# RCSfullschematic1.net
KiCad netlist of a schematic drawn in EAGLE
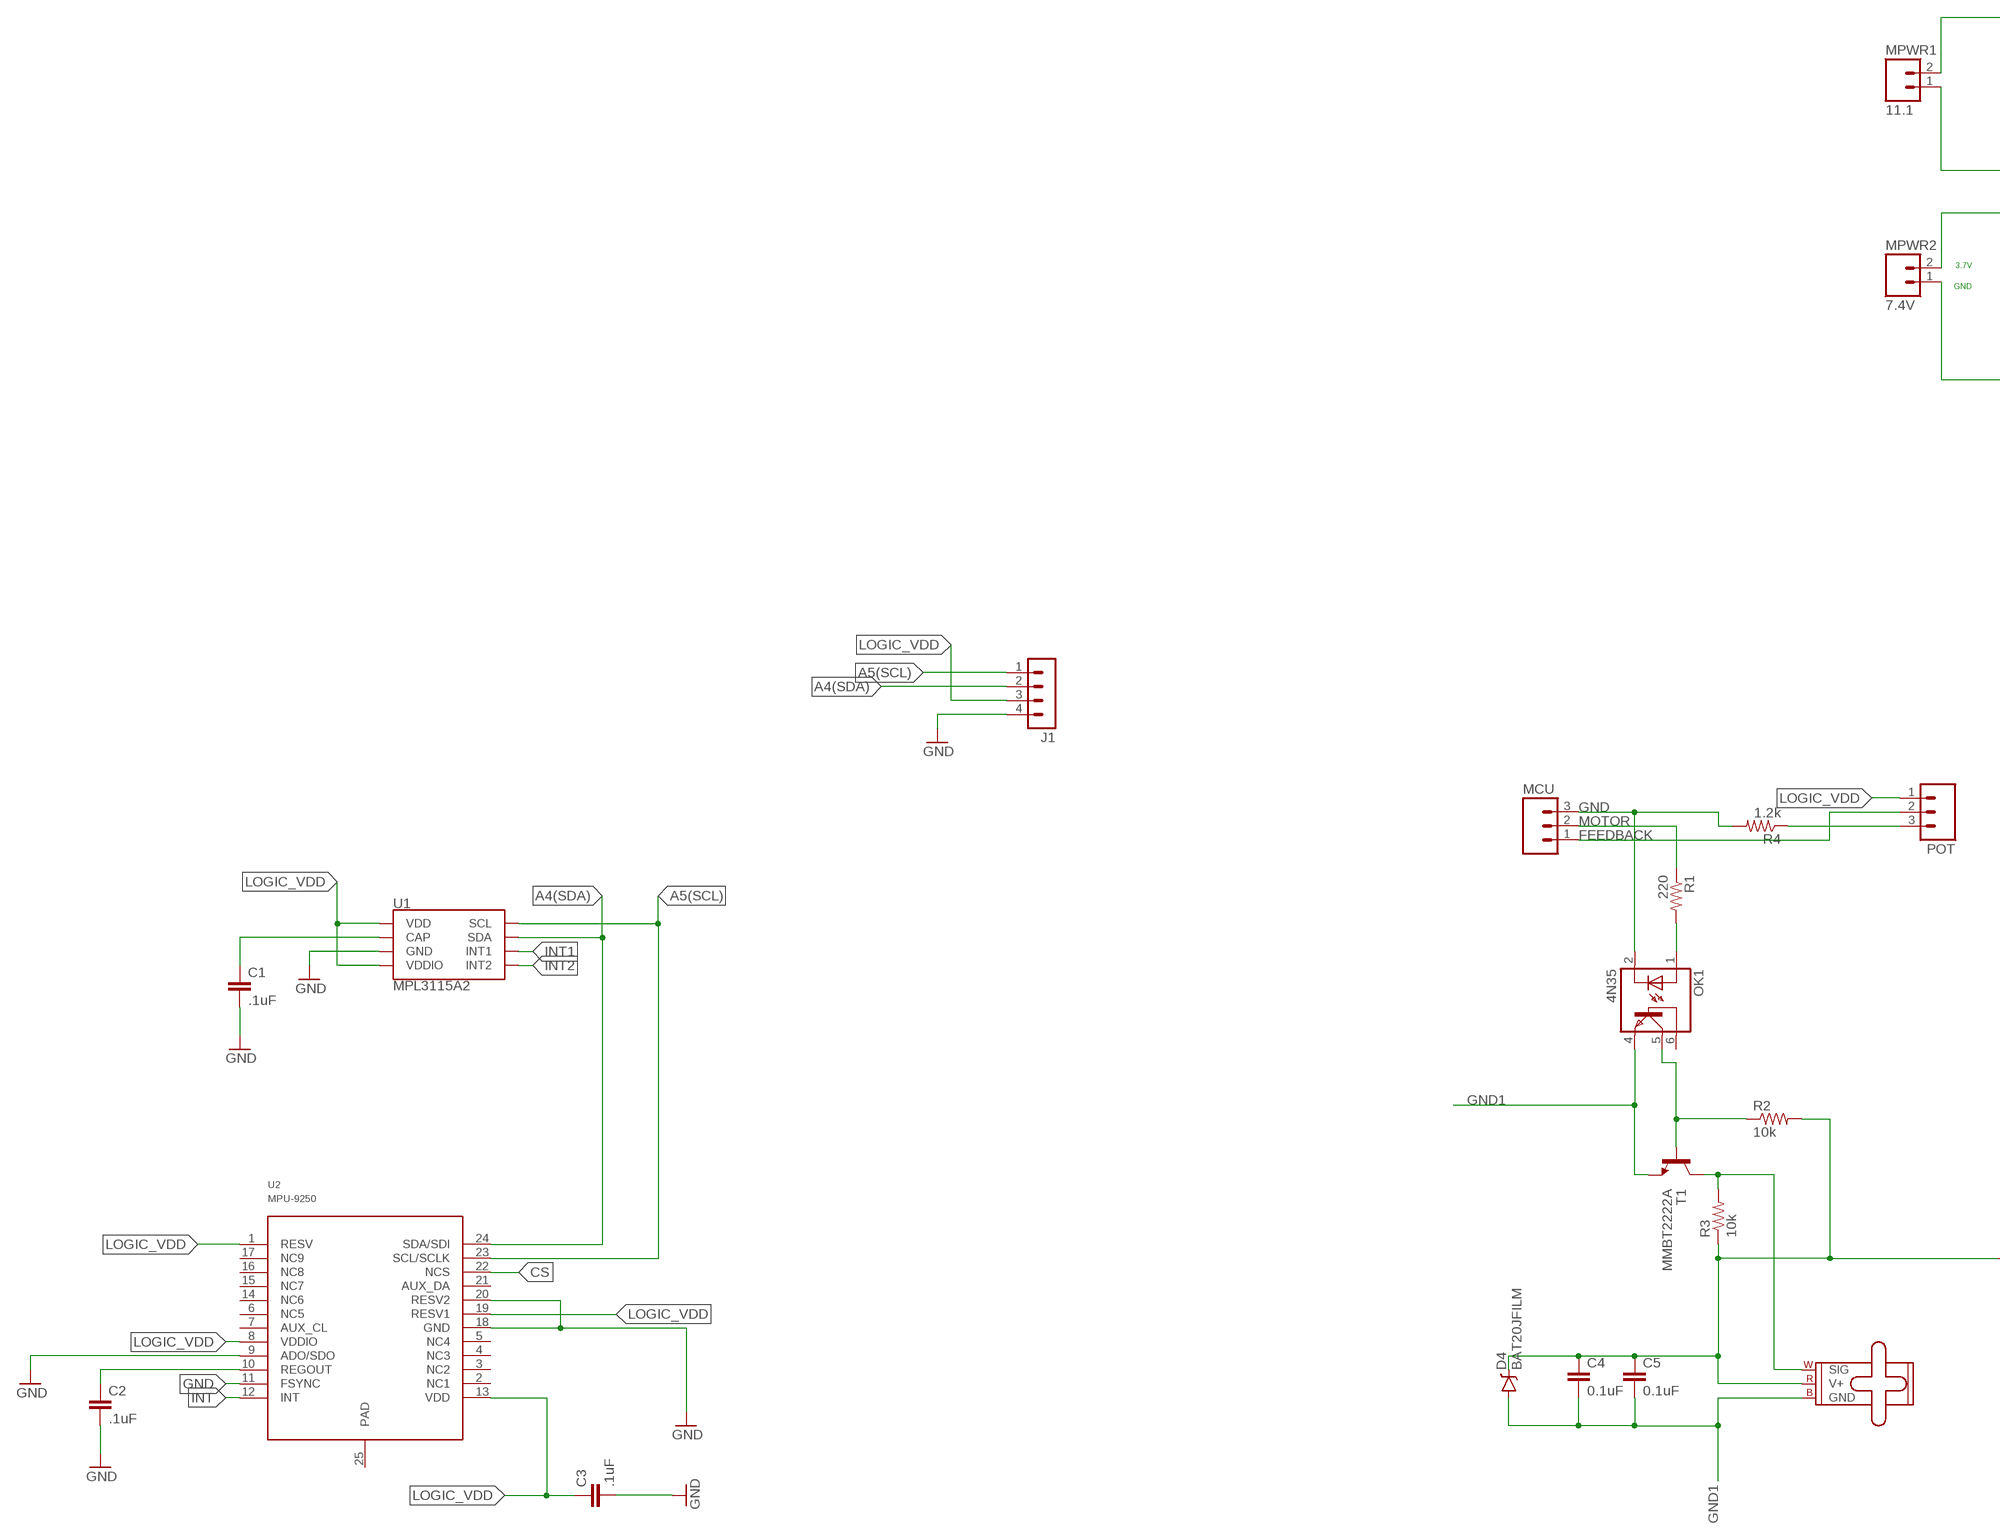
[diagram p0: schematic, sheet 1, part 1 of 2]
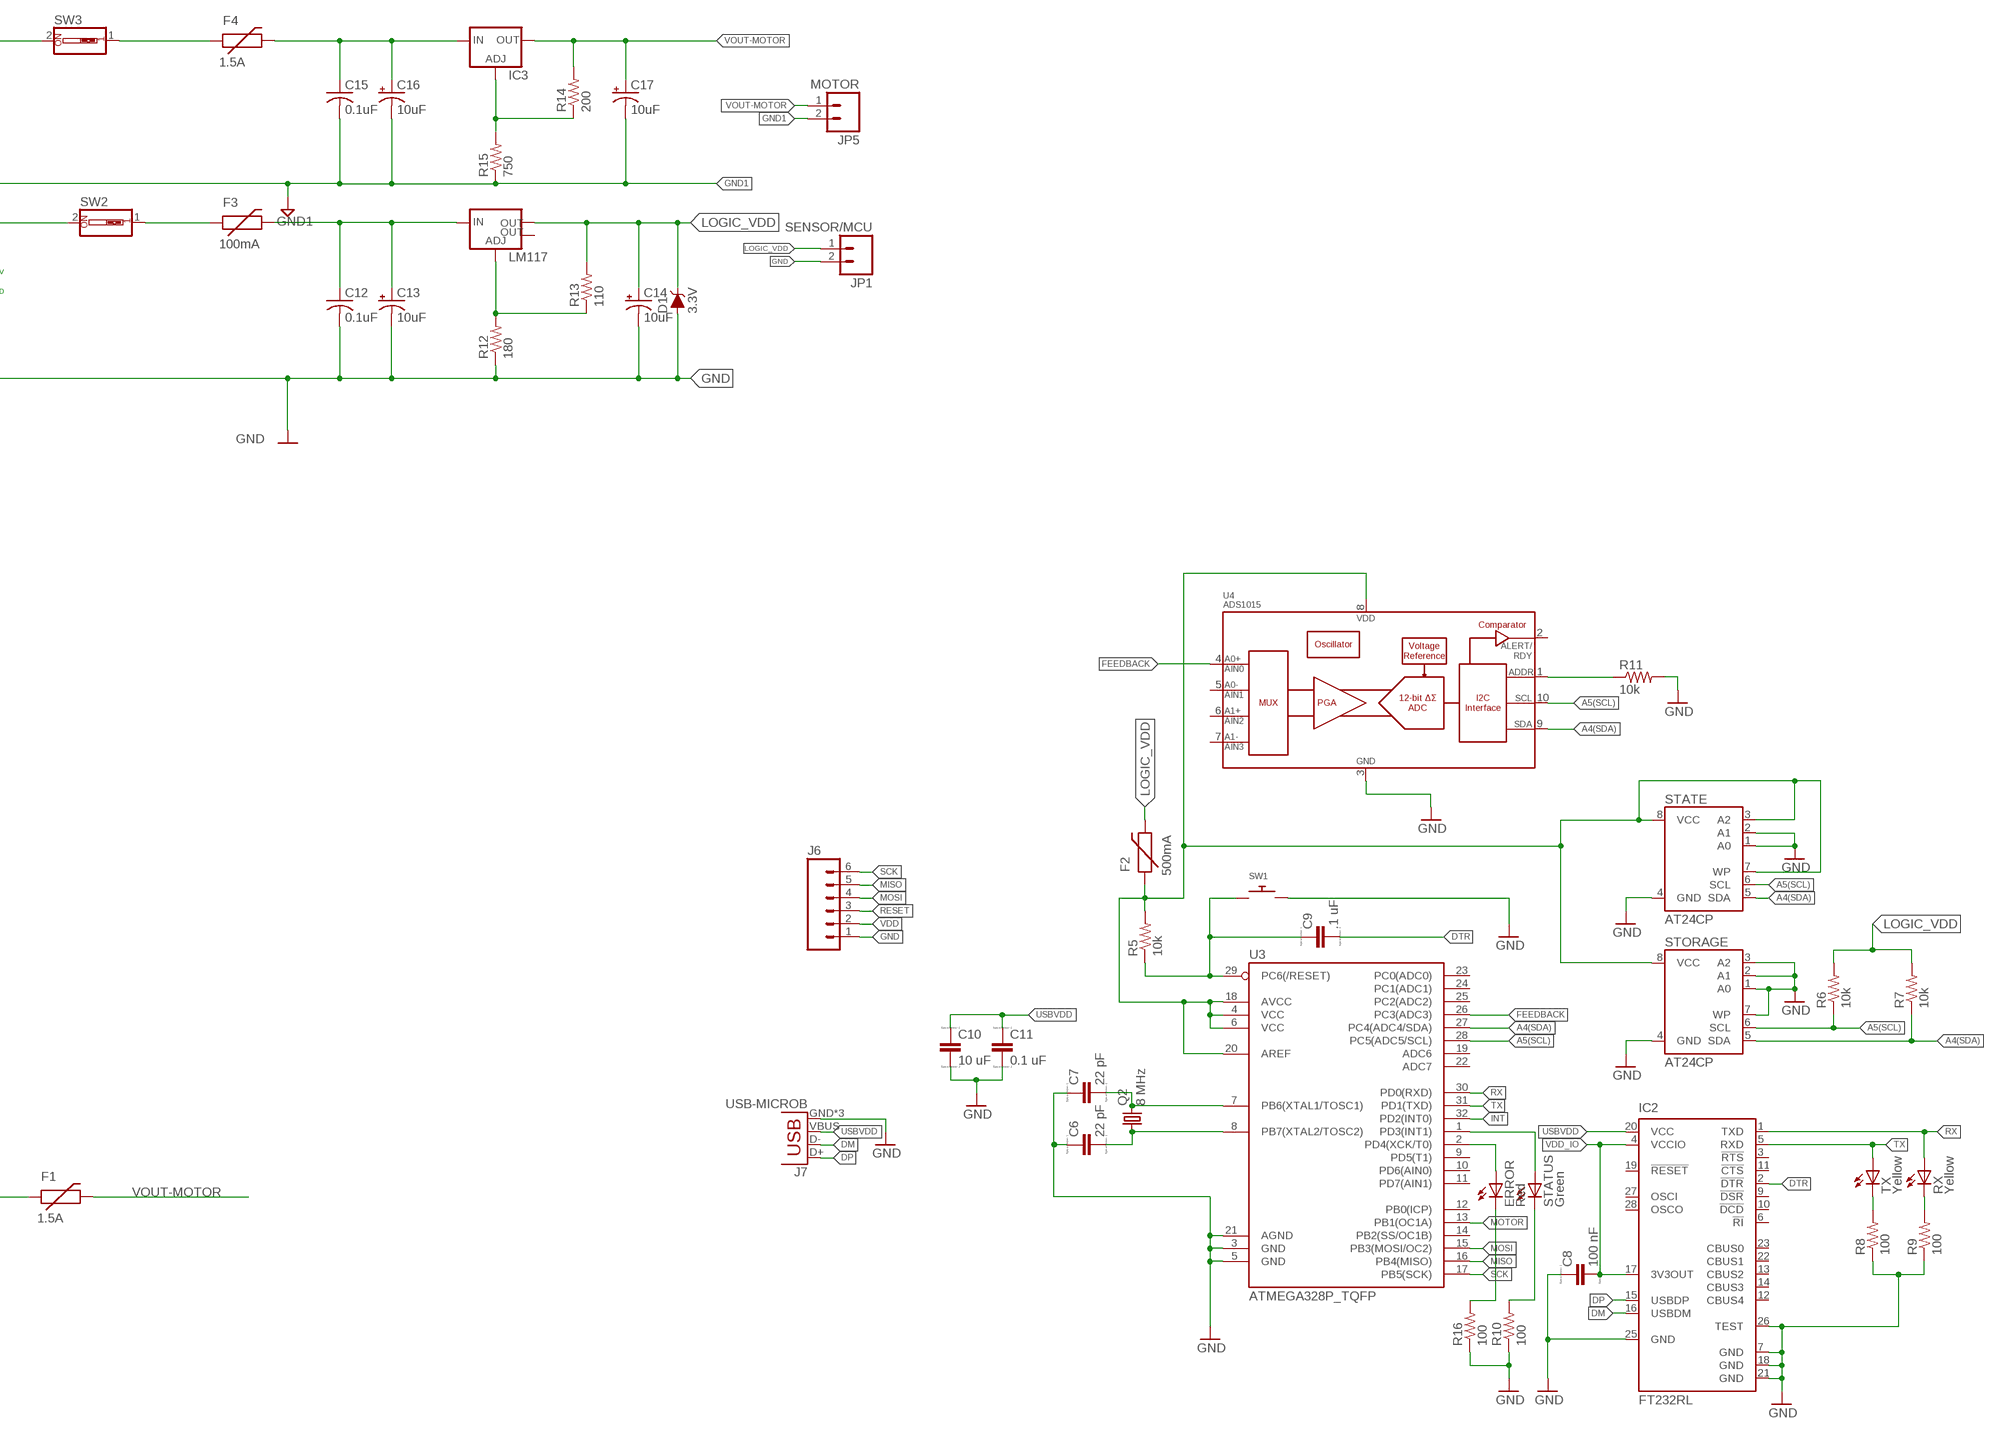
[diagram p1: schematic, sheet 1, part 2 of 2]

(export (version "E")
  (design (tool "Eeschema 10.0.6"))
  (components
    (comp (ref "C1")
      (value ".1uF")
      (footprint "eagle-import:1206")
      (libsource (lib "eagle-import") (part "10UF-1206-6.3V-20%"))
    )
    (comp (ref "C2")
      (value ".1uF")
      (footprint "eagle-import:1206")
      (libsource (lib "eagle-import") (part "10UF-1206-6.3V-20%"))
    )
    (comp (ref "C3")
      (value ".1uF")
      (footprint "eagle-import:1206")
      (libsource (lib "eagle-import") (part "10UF-1206-6.3V-20%"))
    )
    (comp (ref "C4")
      (value "0.1uF")
      (footprint "eagle-import:1206")
      (libsource (lib "eagle-import") (part "CAP1206"))
    )
    (comp (ref "C5")
      (value "0.1uF")
      (footprint "eagle-import:1206")
      (libsource (lib "eagle-import") (part "CAP1206"))
    )
    (comp (ref "C6")
      (value "22 pF")
      (footprint "eagle-import:C1206")
      (libsource (lib "eagle-import") (part "CC1206"))
    )
    (comp (ref "C7")
      (value "22 pF")
      (footprint "eagle-import:C1206")
      (libsource (lib "eagle-import") (part "CC1206"))
    )
    (comp (ref "C8")
      (value "100 nF")
      (footprint "eagle-import:C1206")
      (libsource (lib "eagle-import") (part "CC1206"))
    )
    (comp (ref "C9")
      (value ".1 uF")
      (footprint "eagle-import:C1206")
      (libsource (lib "eagle-import") (part "CC1206"))
    )
    (comp (ref "C10")
      (value "10 uF")
      (footprint "eagle-import:C1206")
      (libsource (lib "eagle-import") (part "CC1206"))
    )
    (comp (ref "C11")
      (value "0.1 uF")
      (footprint "eagle-import:C1206")
      (libsource (lib "eagle-import") (part "CC1206"))
    )
    (comp (ref "C12")
      (value "0.1uF")
      (footprint "eagle-import:C1206")
      (libsource (lib "eagle-import") (part "C-USC1206"))
    )
    (comp (ref "C13")
      (value "10uF")
      (footprint "eagle-import:EIA3216")
      (libsource (lib "eagle-import") (part "10UF-POLAR-EIA3216-16V-10%(TANT)"))
    )
    (comp (ref "C14")
      (value "10uF")
      (footprint "eagle-import:EIA3216")
      (libsource (lib "eagle-import") (part "10UF-POLAR-EIA3216-16V-10%(TANT)"))
    )
    (comp (ref "C15")
      (value "0.1uF")
      (footprint "eagle-import:C1206")
      (libsource (lib "eagle-import") (part "C-USC1206"))
    )
    (comp (ref "C16")
      (value "10uF")
      (footprint "eagle-import:EIA3216")
      (libsource (lib "eagle-import") (part "10UF-POLAR-EIA3216-16V-10%(TANT)"))
    )
    (comp (ref "C17")
      (value "10uF")
      (footprint "eagle-import:EIA3216")
      (libsource (lib "eagle-import") (part "10UF-POLAR-EIA3216-16V-10%(TANT)"))
    )
    (comp (ref "D1")
      (value "3.3V")
      (footprint "eagle-import:SOD-323@2")
      (libsource (lib "eagle-import") (part "DIODE-ZENER-BZT52C3V6S"))
    )
    (comp (ref "D4")
      (value "BAT20JFILM")
      (footprint "eagle-import:SOD-323")
      (libsource (lib "eagle-import") (part "BAT20JFILM"))
    )
    (comp (ref "ERROR")
      (value "Red")
      (footprint "eagle-import:CHIPLED_1206")
      (libsource (lib "eagle-import") (part "LEDCHIPLED_1206"))
    )
    (comp (ref "F1")
      (value "1.5A")
      (footprint "eagle-import:PTC-1206")
      (libsource (lib "eagle-import") (part "PTCSMD"))
    )
    (comp (ref "F2")
      (value "500mA")
      (footprint "eagle-import:PTC-1206")
      (libsource (lib "eagle-import") (part "PTCSMD"))
    )
    (comp (ref "F3")
      (value "100mA")
      (footprint "eagle-import:PTC-1206")
      (libsource (lib "eagle-import") (part "PTCSMD"))
    )
    (comp (ref "F4")
      (value "1.5A")
      (footprint "eagle-import:PTC-1206")
      (libsource (lib "eagle-import") (part "PTCSMD"))
    )
    (comp (ref "IC2")
      (value "FT232RL")
      (footprint "eagle-import:SSOP28")
      (libsource (lib "eagle-import") (part "FT232RL"))
    )
    (comp (ref "IC3")
      (value "LM317TS")
      (footprint "eagle-import:317TS")
      (libsource (lib "eagle-import") (part "LM317TS"))
    )
    (comp (ref "J1")
      (value "MA04-1")
      (footprint "eagle-import:MA04-1")
      (libsource (lib "eagle-import") (part "MA04-1"))
    )
    (comp (ref "J6")
      (value "M06LOCK")
      (footprint "eagle-import:1X06_LOCK")
      (libsource (lib "eagle-import") (part "M06LOCK"))
    )
    (comp (ref "J7")
      (value "USB-MICROB")
      (footprint "eagle-import:USB-MICROB")
      (libsource (lib "eagle-import") (part "USB-MICROB"))
    )
    (comp (ref "JP1")
      (value "SENSOR/MCU")
      (footprint "eagle-import:1X02")
      (libsource (lib "eagle-import") (part "M02PTH"))
    )
    (comp (ref "JP5")
      (value "MOTOR")
      (footprint "eagle-import:1X02")
      (libsource (lib "eagle-import") (part "M02PTH"))
    )
    (comp (ref "LM117")
      (value "V_REG_LM1117SOT223")
      (footprint "eagle-import:SOT223")
      (libsource (lib "eagle-import") (part "V_REG_LM1117SOT223"))
    )
    (comp (ref "MCU")
      (value "M03PTH")
      (footprint "eagle-import:1X03")
      (libsource (lib "eagle-import") (part "M03PTH"))
    )
    (comp (ref "MPWR1")
      (value "11.1")
      (footprint "eagle-import:1X02")
      (libsource (lib "eagle-import") (part "M02PTH"))
    )
    (comp (ref "MPWR2")
      (value "7.4V")
      (footprint "eagle-import:1X02")
      (libsource (lib "eagle-import") (part "M02PTH"))
    )
    (comp (ref "OK1")
      (value "4N35")
      (footprint "eagle-import:DIL06")
      (fields (field (name "MF") "FAIRCHILD SEMICONDUCTOR"))
      (libsource (lib "eagle-import") (part "4N35"))
    )
    (comp (ref "POT")
      (value "M03PTH")
      (footprint "eagle-import:1X03")
      (libsource (lib "eagle-import") (part "M03PTH"))
    )
    (comp (ref "Q2")
      (value "8 MHz")
      (footprint "eagle-import:HC49_S")
      (libsource (lib "eagle-import") (part "CRYSTALHC49S"))
    )
    (comp (ref "R1")
      (value "220")
      (footprint "eagle-import:1206")
      (libsource (lib "eagle-import") (part "RESISTOR1206"))
    )
    (comp (ref "R2")
      (value "10k")
      (footprint "eagle-import:1206")
      (libsource (lib "eagle-import") (part "RESISTOR1206"))
    )
    (comp (ref "R3")
      (value "10k")
      (footprint "eagle-import:1206")
      (libsource (lib "eagle-import") (part "RESISTOR1206"))
    )
    (comp (ref "R4")
      (value "1.2k")
      (footprint "eagle-import:1206")
      (libsource (lib "eagle-import") (part "RESISTOR1206"))
    )
    (comp (ref "R5")
      (value "10k")
      (footprint "eagle-import:R1206")
      (libsource (lib "eagle-import") (part "R-US_R1206"))
    )
    (comp (ref "R6")
      (value "10k")
      (footprint "eagle-import:R1206")
      (libsource (lib "eagle-import") (part "R-US_R1206"))
    )
    (comp (ref "R7")
      (value "10k")
      (footprint "eagle-import:R1206")
      (libsource (lib "eagle-import") (part "R-US_R1206"))
    )
    (comp (ref "R8")
      (value "100")
      (footprint "eagle-import:R1206")
      (libsource (lib "eagle-import") (part "R-US_R1206"))
    )
    (comp (ref "R9")
      (value "100")
      (footprint "eagle-import:R1206")
      (libsource (lib "eagle-import") (part "R-US_R1206"))
    )
    (comp (ref "R10")
      (value "100")
      (footprint "eagle-import:R1206")
      (libsource (lib "eagle-import") (part "R-US_R1206"))
    )
    (comp (ref "R11")
      (value "10k")
      (footprint "eagle-import:R1206")
      (libsource (lib "eagle-import") (part "R-US_R1206"))
    )
    (comp (ref "R12")
      (value "180")
      (footprint "eagle-import:M1206")
      (libsource (lib "eagle-import") (part "rcl_R-US_M1206"))
    )
    (comp (ref "R13")
      (value "110")
      (footprint "eagle-import:M1206")
      (libsource (lib "eagle-import") (part "rcl_R-US_M1206"))
    )
    (comp (ref "R14")
      (value "200")
      (footprint "eagle-import:M1206")
      (libsource (lib "eagle-import") (part "rcl_R-US_M1206"))
    )
    (comp (ref "R15")
      (value "750")
      (footprint "eagle-import:M1206")
      (libsource (lib "eagle-import") (part "rcl_R-US_M1206"))
    )
    (comp (ref "R16")
      (value "100")
      (footprint "eagle-import:R1206")
      (libsource (lib "eagle-import") (part "R-US_R1206"))
    )
    (comp (ref "RX")
      (value "Yellow")
      (footprint "eagle-import:CHIPLED_1206")
      (libsource (lib "eagle-import") (part "LEDCHIPLED_1206"))
    )
    (comp (ref "SERVO")
      (value "SMALL_SERVO")
      (footprint "eagle-import:1X03")
      (libsource (lib "eagle-import") (part "SMALL_SERVO"))
    )
    (comp (ref "STATE")
      (value "AT24CP")
      (footprint "eagle-import:DIL08")
      (fields (field (name "MPN") "AT24C1024BW-SH-B"))
      (libsource (lib "eagle-import") (part "AT24CP"))
    )
    (comp (ref "STATUS")
      (value "Green")
      (footprint "eagle-import:CHIPLED_1206")
      (libsource (lib "eagle-import") (part "LEDCHIPLED_1206"))
    )
    (comp (ref "STORAGE")
      (value "AT24CP")
      (footprint "eagle-import:DIL08")
      (fields (field (name "MPN") "AT24C1024BW-SH-B"))
      (libsource (lib "eagle-import") (part "AT24CP"))
    )
    (comp (ref "SW1")
      (value "SWITCH_PUSHBUTTONSOFTTOUCHSMD_SJ")
      (footprint "eagle-import:PUSHBUTTON_SMD_SJ")
      (libsource (lib "eagle-import") (part "SWITCH_PUSHBUTTONSOFTTOUCHSMD_SJ"))
    )
    (comp (ref "SW2")
      (value "SW_DIP-1")
      (footprint "eagle-import:EDG-01")
      (libsource (lib "eagle-import") (part "SW_DIP-1"))
    )
    (comp (ref "SW3")
      (value "SW_DIP-1")
      (footprint "eagle-import:EDG-01")
      (libsource (lib "eagle-import") (part "SW_DIP-1"))
    )
    (comp (ref "T1")
      (value "MMBT2222A")
      (footprint "eagle-import:SOT23-3")
      (libsource (lib "eagle-import") (part "TRANSISTOR_NPNMMBT2222A"))
    )
    (comp (ref "TX")
      (value "Yellow")
      (footprint "eagle-import:CHIPLED_1206")
      (libsource (lib "eagle-import") (part "LEDCHIPLED_1206"))
    )
    (comp (ref "U1")
      (value "MPL3115A2")
      (footprint "eagle-import:LGA-8")
      (libsource (lib "eagle-import") (part "MPL3115A2"))
    )
    (comp (ref "U2")
      (value "MPU-9250")
      (footprint "eagle-import:LEAD-QFN24")
      (libsource (lib "eagle-import") (part "MPU-9250"))
    )
    (comp (ref "U3")
      (value "ATMEGA328P_TQFP")
      (footprint "eagle-import:TQFP32-08")
      (libsource (lib "eagle-import") (part "ATMEGA328P_TQFP"))
    )
    (comp (ref "U4")
      (value "ADS1015")
      (footprint "eagle-import:MSOP10")
      (libsource (lib "eagle-import") (part "ADS1015"))
    )
  )
  (nets
    (net (code "1") (name "A4(SDA)") (class "Default")
      (node (ref "J1") (pin "2") (pinfunction "2_2") (pintype "passive"))
      (node (ref "R7") (pin "1") (pinfunction "1_1") (pintype "passive"))
      (node (ref "STATE") (pin "5") (pinfunction "SDA_5") (pintype "bidirectional"))
      (node (ref "STORAGE") (pin "5") (pinfunction "SDA_5") (pintype "bidirectional"))
      (node (ref "U1") (pin "7") (pinfunction "SDA_7") (pintype "bidirectional"))
      (node (ref "U2") (pin "24") (pinfunction "SDA/SDI_24") (pintype "bidirectional"))
      (node (ref "U3") (pin "27") (pinfunction "PC4(ADC4/SDA)_27") (pintype "bidirectional"))
      (node (ref "U4") (pin "9") (pinfunction "SDA_9") (pintype "bidirectional"))
    )
    (net (code "2") (name "A5(SCL)") (class "Default")
      (node (ref "J1") (pin "1") (pinfunction "1_1") (pintype "passive"))
      (node (ref "R6") (pin "1") (pinfunction "1_1") (pintype "passive"))
      (node (ref "STATE") (pin "6") (pinfunction "SCL_6") (pintype "bidirectional"))
      (node (ref "STORAGE") (pin "6") (pinfunction "SCL_6") (pintype "bidirectional"))
      (node (ref "U1") (pin "8") (pinfunction "SCL_8") (pintype "bidirectional"))
      (node (ref "U2") (pin "23") (pinfunction "SCL/SCLK_23") (pintype "bidirectional"))
      (node (ref "U3") (pin "28") (pinfunction "PC5(ADC5/SCL)_28") (pintype "bidirectional"))
      (node (ref "U4") (pin "10") (pinfunction "SCL_10") (pintype "bidirectional"))
    )
    (net (code "3") (name "CS") (class "Default")
      (node (ref "U2") (pin "22") (pinfunction "NCS_22") (pintype "bidirectional"))
    )
    (net (code "4") (name "DM") (class "Default")
      (node (ref "IC2") (pin "16") (pinfunction "USBDM_16") (pintype "bidirectional"))
      (node (ref "J7") (pin "D-") (pinfunction "D-_D-") (pintype "bidirectional"))
    )
    (net (code "5") (name "DP") (class "Default")
      (node (ref "IC2") (pin "15") (pinfunction "USBDP_15") (pintype "bidirectional"))
      (node (ref "J7") (pin "D+") (pinfunction "D+_D+") (pintype "bidirectional"))
    )
    (net (code "6") (name "DTR") (class "Default")
      (node (ref "C9") (pin "2") (pinfunction "2_2") (pintype "passive"))
      (node (ref "IC2") (pin "2") (pinfunction "~{DTR}_2") (pintype "output"))
    )
    (net (code "7") (name "FEEDBACK") (class "Default")
      (node (ref "MCU") (pin "1") (pinfunction "1_1") (pintype "passive"))
      (node (ref "POT") (pin "2") (pinfunction "2_2") (pintype "passive"))
      (node (ref "U3") (pin "26") (pinfunction "PC3(ADC3)_26") (pintype "bidirectional"))
      (node (ref "U4") (pin "4") (pinfunction "AIN0_4") (pintype "bidirectional"))
    )
    (net (code "8") (name "GND") (class "Default")
      (node (ref "C1") (pin "2") (pinfunction "2_2") (pintype "passive"))
      (node (ref "C10") (pin "2") (pinfunction "2_2") (pintype "passive"))
      (node (ref "C11") (pin "2") (pinfunction "2_2") (pintype "passive"))
      (node (ref "C12") (pin "2") (pinfunction "2_2") (pintype "passive"))
      (node (ref "C13") (pin "-") (pinfunction "-_-") (pintype "passive"))
      (node (ref "C14") (pin "-") (pinfunction "-_-") (pintype "passive"))
      (node (ref "C2") (pin "2") (pinfunction "2_2") (pintype "passive"))
      (node (ref "C3") (pin "2") (pinfunction "2_2") (pintype "passive"))
      (node (ref "C6") (pin "1") (pinfunction "1_1") (pintype "passive"))
      (node (ref "C7") (pin "1") (pinfunction "1_1") (pintype "passive"))
      (node (ref "C8") (pin "1") (pinfunction "1_1") (pintype "passive"))
      (node (ref "D1") (pin "A") (pinfunction "A_A") (pintype "passive"))
      (node (ref "IC2") (pin "18") (pinfunction "GND_18") (pintype "power_in"))
      (node (ref "IC2") (pin "21") (pinfunction "GND_21") (pintype "power_in"))
      (node (ref "IC2") (pin "25") (pinfunction "GND_25") (pintype "power_in"))
      (node (ref "IC2") (pin "26") (pinfunction "TEST_26") (pintype "input"))
      (node (ref "IC2") (pin "7") (pinfunction "GND_7") (pintype "power_in"))
      (node (ref "J1") (pin "4") (pinfunction "4_4") (pintype "passive"))
      (node (ref "J6") (pin "1") (pinfunction "1_1") (pintype "passive"))
      (node (ref "J7") (pin "GND") (pinfunction "GND_GND") (pintype "bidirectional"))
      (node (ref "J7") (pin "MT1") (pinfunction "GND_MT1") (pintype "bidirectional"))
      (node (ref "J7") (pin "MT2") (pinfunction "GND_MT2") (pintype "bidirectional"))
      (node (ref "JP1") (pin "2") (pinfunction "2_2") (pintype "passive"))
      (node (ref "MCU") (pin "3") (pinfunction "3_3") (pintype "passive"))
      (node (ref "MPWR2") (pin "1") (pinfunction "1_1") (pintype "passive"))
      (node (ref "OK1") (pin "2") (pinfunction "C_2") (pintype "passive"))
      (node (ref "R10") (pin "1") (pinfunction "1_1") (pintype "passive"))
      (node (ref "R11") (pin "2") (pinfunction "2_2") (pintype "passive"))
      (node (ref "R12") (pin "1") (pinfunction "1_1") (pintype "passive"))
      (node (ref "R16") (pin "1") (pinfunction "1_1") (pintype "passive"))
      (node (ref "R4") (pin "2") (pinfunction "2_2") (pintype "passive"))
      (node (ref "R8") (pin "1") (pinfunction "1_1") (pintype "passive"))
      (node (ref "R9") (pin "1") (pinfunction "1_1") (pintype "passive"))
      (node (ref "STATE") (pin "1") (pinfunction "A0_1") (pintype "input"))
      (node (ref "STATE") (pin "2") (pinfunction "A1_2") (pintype "input"))
      (node (ref "STATE") (pin "4") (pinfunction "GND_4") (pintype "power_in"))
      (node (ref "STORAGE") (pin "1") (pinfunction "A0_1") (pintype "input"))
      (node (ref "STORAGE") (pin "2") (pinfunction "A1_2") (pintype "input"))
      (node (ref "STORAGE") (pin "3") (pinfunction "A2_3") (pintype "input"))
      (node (ref "STORAGE") (pin "4") (pinfunction "GND_4") (pintype "power_in"))
      (node (ref "STORAGE") (pin "7") (pinfunction "WP_7") (pintype "input"))
      (node (ref "SW1") (pin "P$2") (pinfunction "P$2_P$2") (pintype "passive"))
      (node (ref "U1") (pin "3") (pinfunction "GND_3") (pintype "power_in"))
      (node (ref "U2") (pin "11") (pinfunction "FSYNC_11") (pintype "bidirectional"))
      (node (ref "U2") (pin "18") (pinfunction "GND_18") (pintype "bidirectional"))
      (node (ref "U2") (pin "20") (pinfunction "RESV2_20") (pintype "bidirectional"))
      (node (ref "U2") (pin "9") (pinfunction "ADO/SDO_9") (pintype "bidirectional"))
      (node (ref "U3") (pin "21") (pinfunction "AGND_21") (pintype "bidirectional"))
      (node (ref "U3") (pin "3") (pinfunction "GND_3") (pintype "bidirectional"))
      (node (ref "U3") (pin "5") (pinfunction "GND_5") (pintype "bidirectional"))
      (node (ref "U4") (pin "3") (pinfunction "VSS_3") (pintype "bidirectional"))
    )
    (net (code "9") (name "GND1") (class "Default")
      (node (ref "C15") (pin "2") (pinfunction "2_2") (pintype "passive"))
      (node (ref "C16") (pin "-") (pinfunction "-_-") (pintype "passive"))
      (node (ref "C17") (pin "-") (pinfunction "-_-") (pintype "passive"))
      (node (ref "C4") (pin "2") (pinfunction "2_2") (pintype "passive"))
      (node (ref "C5") (pin "2") (pinfunction "2_2") (pintype "passive"))
      (node (ref "D4") (pin "A") (pinfunction "A_A") (pintype "passive"))
      (node (ref "JP5") (pin "2") (pinfunction "2_2") (pintype "passive"))
      (node (ref "MPWR1") (pin "1") (pinfunction "1_1") (pintype "passive"))
      (node (ref "OK1") (pin "4") (pinfunction "EMI_4") (pintype "passive"))
      (node (ref "R15") (pin "1") (pinfunction "1_1") (pintype "passive"))
      (node (ref "SERVO") (pin "3") (pinfunction "GND_3") (pintype "bidirectional"))
      (node (ref "T1") (pin "2") (pinfunction "E_2") (pintype "passive"))
    )
    (net (code "10") (name "INT") (class "Default")
      (node (ref "U2") (pin "12") (pinfunction "INT_12") (pintype "bidirectional"))
      (node (ref "U3") (pin "32") (pinfunction "PD2(INT0)_32") (pintype "bidirectional"))
    )
    (net (code "11") (name "INT1") (class "Default")
      (node (ref "U1") (pin "6") (pinfunction "INT1_6") (pintype "output"))
    )
    (net (code "12") (name "INT2") (class "Default")
      (node (ref "U1") (pin "5") (pinfunction "INT2_5") (pintype "output"))
    )
    (net (code "13") (name "LOGIC_VDD") (class "Default")
      (node (ref "C14") (pin "+") (pinfunction "+_+") (pintype "passive"))
      (node (ref "C3") (pin "1") (pinfunction "1_1") (pintype "passive"))
      (node (ref "D1") (pin "C") (pinfunction "C_C") (pintype "passive"))
      (node (ref "F2") (pin "2") (pinfunction "2_2") (pintype "bidirectional"))
      (node (ref "J1") (pin "3") (pinfunction "3_3") (pintype "passive"))
      (node (ref "JP1") (pin "1") (pinfunction "1_1") (pintype "passive"))
      (node (ref "LM117") (pin "2") (pinfunction "OUT_2") (pintype "output"))
      (node (ref "POT") (pin "1") (pinfunction "1_1") (pintype "passive"))
      (node (ref "R13") (pin "2") (pinfunction "2_2") (pintype "passive"))
      (node (ref "R6") (pin "2") (pinfunction "2_2") (pintype "passive"))
      (node (ref "R7") (pin "2") (pinfunction "2_2") (pintype "passive"))
      (node (ref "U1") (pin "1") (pinfunction "VDD_1") (pintype "power_in"))
      (node (ref "U1") (pin "4") (pinfunction "VDDIO_4") (pintype "power_in"))
      (node (ref "U2") (pin "1") (pinfunction "RESV_1") (pintype "bidirectional"))
      (node (ref "U2") (pin "13") (pinfunction "VDD_13") (pintype "bidirectional"))
      (node (ref "U2") (pin "19") (pinfunction "RESV1_19") (pintype "bidirectional"))
      (node (ref "U2") (pin "8") (pinfunction "VDDIO_8") (pintype "bidirectional"))
    )
    (net (code "14") (name "MISO") (class "Default")
      (node (ref "J6") (pin "5") (pinfunction "5_5") (pintype "passive"))
      (node (ref "U3") (pin "16") (pinfunction "PB4(MISO)_16") (pintype "bidirectional"))
    )
    (net (code "15") (name "MOSI") (class "Default")
      (node (ref "J6") (pin "4") (pinfunction "4_4") (pintype "passive"))
      (node (ref "U3") (pin "15") (pinfunction "PB3(MOSI/OC2)_15") (pintype "bidirectional"))
    )
    (net (code "16") (name "MOTOR") (class "Default")
      (node (ref "MCU") (pin "2") (pinfunction "2_2") (pintype "passive"))
      (node (ref "R1") (pin "1") (pinfunction "1_1") (pintype "passive"))
      (node (ref "U3") (pin "13") (pinfunction "PB1(OC1A)_13") (pintype "bidirectional"))
    )
    (net (code "17") (name "Net-(ERROR-PadC)") (class "Default")
      (node (ref "ERROR") (pin "C") (pinfunction "C_C") (pintype "passive"))
      (node (ref "R16") (pin "2") (pinfunction "2_2") (pintype "passive"))
    )
    (net (code "18") (name "Net-(F3-Pad1)") (class "Default")
      (node (ref "F3") (pin "1") (pinfunction "1_1") (pintype "bidirectional"))
      (node (ref "SW2") (pin "1") (pinfunction "1_1") (pintype "passive"))
    )
    (net (code "19") (name "Net-(F4-Pad1)") (class "Default")
      (node (ref "F4") (pin "1") (pinfunction "1_1") (pintype "bidirectional"))
      (node (ref "SW3") (pin "1") (pinfunction "1_1") (pintype "passive"))
    )
    (net (code "20") (name "Net-(IC3-ADJ)") (class "Default")
      (node (ref "IC3") (pin "1") (pinfunction "ADJ_1") (pintype "input"))
      (node (ref "R14") (pin "1") (pinfunction "1_1") (pintype "passive"))
      (node (ref "R15") (pin "2") (pinfunction "2_2") (pintype "passive"))
    )
    (net (code "21") (name "Net-(IC3-IN)") (class "Default")
      (node (ref "C15") (pin "1") (pinfunction "1_1") (pintype "passive"))
      (node (ref "C16") (pin "+") (pinfunction "+_+") (pintype "passive"))
      (node (ref "F4") (pin "2") (pinfunction "2_2") (pintype "bidirectional"))
      (node (ref "IC3") (pin "3") (pinfunction "IN_3") (pintype "input"))
    )
    (net (code "22") (name "Net-(LM117-ADJ)") (class "Default")
      (node (ref "LM117") (pin "1") (pinfunction "ADJ_1") (pintype "input"))
      (node (ref "R12") (pin "2") (pinfunction "2_2") (pintype "passive"))
      (node (ref "R13") (pin "1") (pinfunction "1_1") (pintype "passive"))
    )
    (net (code "23") (name "Net-(LM117-IN)") (class "Default")
      (node (ref "C12") (pin "1") (pinfunction "1_1") (pintype "passive"))
      (node (ref "C13") (pin "+") (pinfunction "+_+") (pintype "passive"))
      (node (ref "F3") (pin "2") (pinfunction "2_2") (pintype "bidirectional"))
      (node (ref "LM117") (pin "3") (pinfunction "IN_3") (pintype "input"))
    )
    (net (code "24") (name "Net-(MPWR1-Pad2)") (class "Default")
      (node (ref "MPWR1") (pin "2") (pinfunction "2_2") (pintype "passive"))
      (node (ref "SW3") (pin "2") (pinfunction "2_2") (pintype "passive"))
    )
    (net (code "25") (name "Net-(MPWR2-Pad2)") (class "Default")
      (node (ref "MPWR2") (pin "2") (pinfunction "2_2") (pintype "passive"))
      (node (ref "SW2") (pin "2") (pinfunction "2_2") (pintype "passive"))
    )
    (net (code "26") (name "Net-(OK1-A)") (class "Default")
      (node (ref "OK1") (pin "1") (pinfunction "A_1") (pintype "passive"))
      (node (ref "R1") (pin "2") (pinfunction "2_2") (pintype "passive"))
    )
    (net (code "27") (name "Net-(OK1-COL)") (class "Default")
      (node (ref "OK1") (pin "5") (pinfunction "COL_5") (pintype "passive"))
      (node (ref "R2") (pin "1") (pinfunction "1_1") (pintype "passive"))
      (node (ref "T1") (pin "1") (pinfunction "B_1") (pintype "passive"))
    )
    (net (code "28") (name "Net-(POT-Pad3)") (class "Default")
      (node (ref "POT") (pin "3") (pinfunction "3_3") (pintype "passive"))
      (node (ref "R4") (pin "1") (pinfunction "1_1") (pintype "passive"))
    )
    (net (code "29") (name "Net-(R8-Pad2)") (class "Default")
      (node (ref "R8") (pin "2") (pinfunction "2_2") (pintype "passive"))
      (node (ref "TX") (pin "C") (pinfunction "C_C") (pintype "passive"))
    )
    (net (code "30") (name "Net-(R9-Pad2)") (class "Default")
      (node (ref "R9") (pin "2") (pinfunction "2_2") (pintype "passive"))
      (node (ref "RX") (pin "C") (pinfunction "C_C") (pintype "passive"))
    )
    (net (code "31") (name "Net-(R10-Pad2)") (class "Default")
      (node (ref "R10") (pin "2") (pinfunction "2_2") (pintype "passive"))
      (node (ref "STATUS") (pin "C") (pinfunction "C_C") (pintype "passive"))
    )
    (net (code "32") (name "Net-(SERVO-SIG)") (class "Default")
      (node (ref "R3") (pin "2") (pinfunction "2_2") (pintype "passive"))
      (node (ref "SERVO") (pin "1") (pinfunction "SIG_1") (pintype "bidirectional"))
      (node (ref "T1") (pin "3") (pinfunction "C_3") (pintype "passive"))
    )
    (net (code "33") (name "Net-(SERVO-V+)") (class "Default")
      (node (ref "C4") (pin "1") (pinfunction "1_1") (pintype "passive"))
      (node (ref "C5") (pin "1") (pinfunction "1_1") (pintype "passive"))
      (node (ref "D4") (pin "C") (pinfunction "C_C") (pintype "passive"))
      (node (ref "F1") (pin "1") (pinfunction "1_1") (pintype "bidirectional"))
      (node (ref "R2") (pin "2") (pinfunction "2_2") (pintype "passive"))
      (node (ref "R3") (pin "1") (pinfunction "1_1") (pintype "passive"))
      (node (ref "SERVO") (pin "2") (pinfunction "V+_2") (pintype "bidirectional"))
    )
    (net (code "34") (name "Net-(STATE-A2)") (class "Default")
      (node (ref "F2") (pin "1") (pinfunction "1_1") (pintype "bidirectional"))
      (node (ref "R5") (pin "2") (pinfunction "2_2") (pintype "passive"))
      (node (ref "STATE") (pin "3") (pinfunction "A2_3") (pintype "input"))
      (node (ref "STATE") (pin "7") (pinfunction "WP_7") (pintype "input"))
      (node (ref "STATE") (pin "8") (pinfunction "VCC_8") (pintype "power_in"))
      (node (ref "STORAGE") (pin "8") (pinfunction "VCC_8") (pintype "power_in"))
      (node (ref "U3") (pin "18") (pinfunction "AVCC_18") (pintype "bidirectional"))
      (node (ref "U3") (pin "20") (pinfunction "AREF_20") (pintype "bidirectional"))
      (node (ref "U3") (pin "4") (pinfunction "VCC_4") (pintype "bidirectional"))
      (node (ref "U3") (pin "6") (pinfunction "VCC_6") (pintype "bidirectional"))
      (node (ref "U4") (pin "8") (pinfunction "VDD_8") (pintype "bidirectional"))
    )
    (net (code "35") (name "Net-(U1-CAP)") (class "Default")
      (node (ref "C1") (pin "1") (pinfunction "1_1") (pintype "passive"))
      (node (ref "U1") (pin "2") (pinfunction "CAP_2") (pintype "power_in"))
    )
    (net (code "36") (name "Net-(U2-REGOUT)") (class "Default")
      (node (ref "C2") (pin "1") (pinfunction "1_1") (pintype "passive"))
      (node (ref "U2") (pin "10") (pinfunction "REGOUT_10") (pintype "bidirectional"))
    )
    (net (code "37") (name "Net-(U3-PB6(XTAL1{slash}TOSC1))") (class "Default")
      (node (ref "C7") (pin "2") (pinfunction "2_2") (pintype "passive"))
      (node (ref "Q2") (pin "2") (pinfunction "2_2") (pintype "passive"))
      (node (ref "U3") (pin "7") (pinfunction "PB6(XTAL1/TOSC1)_7") (pintype "bidirectional"))
    )
    (net (code "38") (name "Net-(U3-PB7(XTAL2{slash}TOSC2))") (class "Default")
      (node (ref "C6") (pin "2") (pinfunction "2_2") (pintype "passive"))
      (node (ref "Q2") (pin "1") (pinfunction "1_1") (pintype "passive"))
      (node (ref "U3") (pin "8") (pinfunction "PB7(XTAL2/TOSC2)_8") (pintype "bidirectional"))
    )
    (net (code "39") (name "Net-(U3-PD3(INT1))") (class "Default")
      (node (ref "STATUS") (pin "A") (pinfunction "A_A") (pintype "passive"))
      (node (ref "U3") (pin "1") (pinfunction "PD3(INT1)_1") (pintype "bidirectional"))
    )
    (net (code "40") (name "Net-(U3-PD4(XCK{slash}T0))") (class "Default")
      (node (ref "ERROR") (pin "A") (pinfunction "A_A") (pintype "passive"))
      (node (ref "U3") (pin "2") (pinfunction "PD4(XCK/T0)_2") (pintype "bidirectional"))
    )
    (net (code "41") (name "Net-(U4-ADDR)") (class "Default")
      (node (ref "R11") (pin "1") (pinfunction "1_1") (pintype "passive"))
      (node (ref "U4") (pin "1") (pinfunction "ADDR_1") (pintype "bidirectional"))
    )
    (net (code "42") (name "RESET") (class "Default")
      (node (ref "C9") (pin "1") (pinfunction "1_1") (pintype "passive"))
      (node (ref "J6") (pin "3") (pinfunction "3_3") (pintype "passive"))
      (node (ref "R5") (pin "1") (pinfunction "1_1") (pintype "passive"))
      (node (ref "SW1") (pin "P$1") (pinfunction "P$1_P$1") (pintype "passive"))
      (node (ref "U3") (pin "29") (pinfunction "PC6(/RESET)_29") (pintype "bidirectional"))
    )
    (net (code "43") (name "RX") (class "Default")
      (node (ref "IC2") (pin "1") (pinfunction "TXD_1") (pintype "output"))
      (node (ref "RX") (pin "A") (pinfunction "A_A") (pintype "passive"))
      (node (ref "U3") (pin "30") (pinfunction "PD0(RXD)_30") (pintype "bidirectional"))
    )
    (net (code "44") (name "SCK") (class "Default")
      (node (ref "J6") (pin "6") (pinfunction "6_6") (pintype "passive"))
      (node (ref "U3") (pin "17") (pinfunction "PB5(SCK)_17") (pintype "bidirectional"))
    )
    (net (code "45") (name "TX") (class "Default")
      (node (ref "IC2") (pin "5") (pinfunction "RXD_5") (pintype "input"))
      (node (ref "TX") (pin "A") (pinfunction "A_A") (pintype "passive"))
      (node (ref "U3") (pin "31") (pinfunction "PD1(TXD)_31") (pintype "bidirectional"))
    )
    (net (code "46") (name "USBVDD") (class "Default")
      (node (ref "C10") (pin "1") (pinfunction "1_1") (pintype "passive"))
      (node (ref "C11") (pin "1") (pinfunction "1_1") (pintype "passive"))
      (node (ref "IC2") (pin "20") (pinfunction "VCC_20") (pintype "power_in"))
      (node (ref "J7") (pin "VBUS") (pinfunction "VBUS_VBUS") (pintype "bidirectional"))
    )
    (net (code "47") (name "VDD") (class "Default")
      (node (ref "J6") (pin "2") (pinfunction "2_2") (pintype "passive"))
    )
    (net (code "48") (name "VDD_IO") (class "Default")
      (node (ref "C8") (pin "2") (pinfunction "2_2") (pintype "passive"))
      (node (ref "IC2") (pin "17") (pinfunction "3V3OUT_17") (pintype "output"))
      (node (ref "IC2") (pin "4") (pinfunction "VCCIO_4") (pintype "power_in"))
    )
    (net (code "49") (name "VOUT-MOTOR") (class "Default")
      (node (ref "C17") (pin "+") (pinfunction "+_+") (pintype "passive"))
      (node (ref "F1") (pin "2") (pinfunction "2_2") (pintype "bidirectional"))
      (node (ref "IC3") (pin "2") (pinfunction "OUT_2") (pintype "passive"))
      (node (ref "JP5") (pin "1") (pinfunction "1_1") (pintype "passive"))
      (node (ref "R14") (pin "2") (pinfunction "2_2") (pintype "passive"))
    )
    (net (code "50") (name "unconnected-(IC2-CBUS0-Pad23)") (class "Default")
      (node (ref "IC2") (pin "23") (pinfunction "CBUS0_23") (pintype "bidirectional"))
    )
    (net (code "51") (name "unconnected-(IC2-CBUS1-Pad22)") (class "Default")
      (node (ref "IC2") (pin "22") (pinfunction "CBUS1_22") (pintype "bidirectional"))
    )
    (net (code "52") (name "unconnected-(IC2-CBUS2-Pad13)") (class "Default")
      (node (ref "IC2") (pin "13") (pinfunction "CBUS2_13") (pintype "bidirectional"))
    )
    (net (code "53") (name "unconnected-(IC2-CBUS3-Pad14)") (class "Default")
      (node (ref "IC2") (pin "14") (pinfunction "CBUS3_14") (pintype "bidirectional"))
    )
    (net (code "54") (name "unconnected-(IC2-CBUS4-Pad12)") (class "Default")
      (node (ref "IC2") (pin "12") (pinfunction "CBUS4_12") (pintype "bidirectional"))
    )
    (net (code "55") (name "unconnected-(IC2-OSCI-Pad27)") (class "Default")
      (node (ref "IC2") (pin "27") (pinfunction "OSCI_27") (pintype "input"))
    )
    (net (code "56") (name "unconnected-(IC2-OSCO-Pad28)") (class "Default")
      (node (ref "IC2") (pin "28") (pinfunction "OSCO_28") (pintype "output"))
    )
    (net (code "57") (name "unconnected-(IC2-~{CTS}-Pad11)") (class "Default")
      (node (ref "IC2") (pin "11") (pinfunction "~{CTS}_11") (pintype "input"))
    )
    (net (code "58") (name "unconnected-(IC2-~{DCD}-Pad10)") (class "Default")
      (node (ref "IC2") (pin "10") (pinfunction "~{DCD}_10") (pintype "input"))
    )
    (net (code "59") (name "unconnected-(IC2-~{DSR}-Pad9)") (class "Default")
      (node (ref "IC2") (pin "9") (pinfunction "~{DSR}_9") (pintype "input"))
    )
    (net (code "60") (name "unconnected-(IC2-~{RESET}-Pad19)") (class "Default")
      (node (ref "IC2") (pin "19") (pinfunction "~{RESET}_19") (pintype "input"))
    )
    (net (code "61") (name "unconnected-(IC2-~{RI}-Pad6)") (class "Default")
      (node (ref "IC2") (pin "6") (pinfunction "~{RI}_6") (pintype "input"))
    )
    (net (code "62") (name "unconnected-(IC2-~{RTS}-Pad3)") (class "Default")
      (node (ref "IC2") (pin "3") (pinfunction "~{RTS}_3") (pintype "output"))
    )
    (net (code "63") (name "unconnected-(LM117-OUT-Pad4)") (class "Default")
      (node (ref "LM117") (pin "4") (pinfunction "OUT_4") (pintype "output"))
    )
    (net (code "64") (name "unconnected-(OK1-BAS-Pad6)") (class "Default")
      (node (ref "OK1") (pin "6") (pinfunction "BAS_6") (pintype "passive"))
    )
    (net (code "65") (name "unconnected-(U2-AUX_CL-Pad7)") (class "Default")
      (node (ref "U2") (pin "7") (pinfunction "AUX_CL_7") (pintype "bidirectional"))
    )
    (net (code "66") (name "unconnected-(U2-AUX_DA-Pad21)") (class "Default")
      (node (ref "U2") (pin "21") (pinfunction "AUX_DA_21") (pintype "bidirectional"))
    )
    (net (code "67") (name "unconnected-(U2-NC1-Pad2)") (class "Default")
      (node (ref "U2") (pin "2") (pinfunction "NC1_2") (pintype "bidirectional"))
    )
    (net (code "68") (name "unconnected-(U2-NC2-Pad3)") (class "Default")
      (node (ref "U2") (pin "3") (pinfunction "NC2_3") (pintype "bidirectional"))
    )
    (net (code "69") (name "unconnected-(U2-NC3-Pad4)") (class "Default")
      (node (ref "U2") (pin "4") (pinfunction "NC3_4") (pintype "bidirectional"))
    )
    (net (code "70") (name "unconnected-(U2-NC4-Pad5)") (class "Default")
      (node (ref "U2") (pin "5") (pinfunction "NC4_5") (pintype "bidirectional"))
    )
    (net (code "71") (name "unconnected-(U2-NC5-Pad6)") (class "Default")
      (node (ref "U2") (pin "6") (pinfunction "NC5_6") (pintype "bidirectional"))
    )
    (net (code "72") (name "unconnected-(U2-NC6-Pad14)") (class "Default")
      (node (ref "U2") (pin "14") (pinfunction "NC6_14") (pintype "bidirectional"))
    )
    (net (code "73") (name "unconnected-(U2-NC7-Pad15)") (class "Default")
      (node (ref "U2") (pin "15") (pinfunction "NC7_15") (pintype "bidirectional"))
    )
    (net (code "74") (name "unconnected-(U2-NC8-Pad16)") (class "Default")
      (node (ref "U2") (pin "16") (pinfunction "NC8_16") (pintype "bidirectional"))
    )
    (net (code "75") (name "unconnected-(U2-NC9-Pad17)") (class "Default")
      (node (ref "U2") (pin "17") (pinfunction "NC9_17") (pintype "bidirectional"))
    )
    (net (code "76") (name "unconnected-(U2-PAD-Pad25)") (class "Default")
      (node (ref "U2") (pin "25") (pinfunction "PAD_25") (pintype "bidirectional"))
    )
    (net (code "77") (name "unconnected-(U3-ADC6-Pad19)") (class "Default")
      (node (ref "U3") (pin "19") (pinfunction "ADC6_19") (pintype "bidirectional"))
    )
    (net (code "78") (name "unconnected-(U3-ADC7-Pad22)") (class "Default")
      (node (ref "U3") (pin "22") (pinfunction "ADC7_22") (pintype "bidirectional"))
    )
    (net (code "79") (name "unconnected-(U3-PB0(ICP)-Pad12)") (class "Default")
      (node (ref "U3") (pin "12") (pinfunction "PB0(ICP)_12") (pintype "bidirectional"))
    )
    (net (code "80") (name "unconnected-(U3-PB2(SS{slash}OC1B)-Pad14)") (class "Default")
      (node (ref "U3") (pin "14") (pinfunction "PB2(SS/OC1B)_14") (pintype "bidirectional"))
    )
    (net (code "81") (name "unconnected-(U3-PC0(ADC0)-Pad23)") (class "Default")
      (node (ref "U3") (pin "23") (pinfunction "PC0(ADC0)_23") (pintype "bidirectional"))
    )
    (net (code "82") (name "unconnected-(U3-PC1(ADC1)-Pad24)") (class "Default")
      (node (ref "U3") (pin "24") (pinfunction "PC1(ADC1)_24") (pintype "bidirectional"))
    )
    (net (code "83") (name "unconnected-(U3-PC2(ADC2)-Pad25)") (class "Default")
      (node (ref "U3") (pin "25") (pinfunction "PC2(ADC2)_25") (pintype "bidirectional"))
    )
    (net (code "84") (name "unconnected-(U3-PD5(T1)-Pad9)") (class "Default")
      (node (ref "U3") (pin "9") (pinfunction "PD5(T1)_9") (pintype "bidirectional"))
    )
    (net (code "85") (name "unconnected-(U3-PD6(AIN0)-Pad10)") (class "Default")
      (node (ref "U3") (pin "10") (pinfunction "PD6(AIN0)_10") (pintype "bidirectional"))
    )
    (net (code "86") (name "unconnected-(U3-PD7(AIN1)-Pad11)") (class "Default")
      (node (ref "U3") (pin "11") (pinfunction "PD7(AIN1)_11") (pintype "bidirectional"))
    )
    (net (code "87") (name "unconnected-(U4-AIN1-Pad5)") (class "Default")
      (node (ref "U4") (pin "5") (pinfunction "AIN1_5") (pintype "bidirectional"))
    )
    (net (code "88") (name "unconnected-(U4-AIN2-Pad6)") (class "Default")
      (node (ref "U4") (pin "6") (pinfunction "AIN2_6") (pintype "bidirectional"))
    )
    (net (code "89") (name "unconnected-(U4-AIN3-Pad7)") (class "Default")
      (node (ref "U4") (pin "7") (pinfunction "AIN3_7") (pintype "bidirectional"))
    )
    (net (code "90") (name "unconnected-(U4-ALERT{slash}RDY-Pad2)") (class "Default")
      (node (ref "U4") (pin "2") (pinfunction "ALERT/RDY_2") (pintype "bidirectional"))
    )
  )
)
